# LV_power.net
KiCad netlist of a schematic drawn in Altium Designer
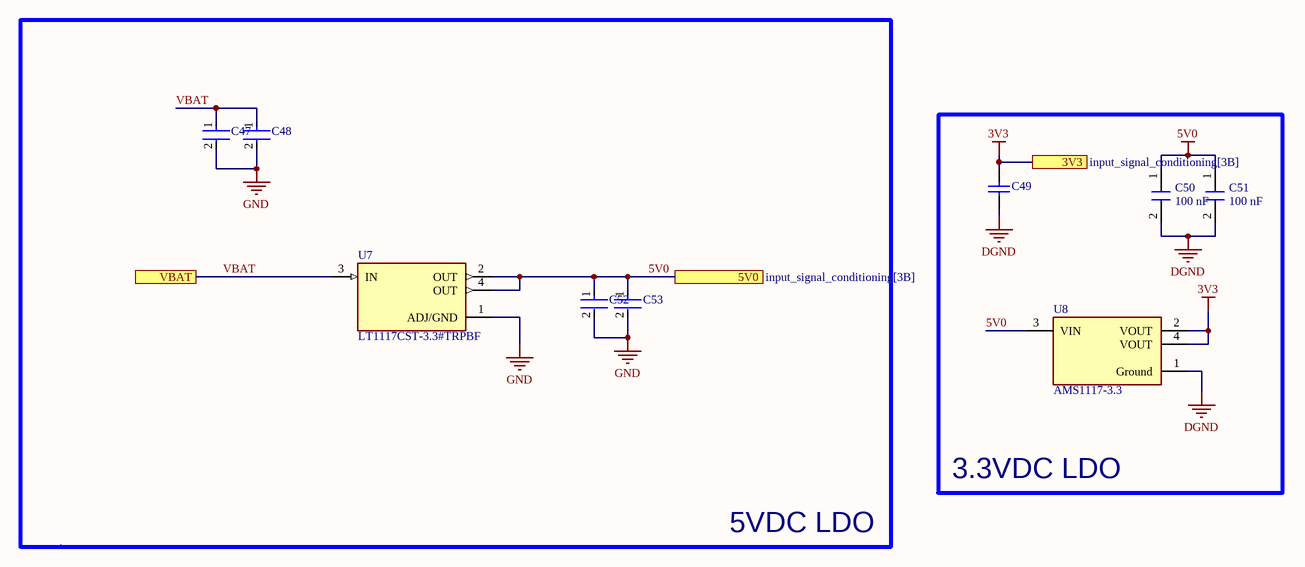
[diagram p0: LV_power.SchDoc]

(export (version "E")
  (design (tool "Eeschema 10.0.6"))
  (components
    (comp (ref "C47")
      (value "CC0805MKX5R8BB226")
      (footprint "FP-CC0805-0_2-1_45-IPC_C")
      (description "CAP CER 22UF 25V X5R 0805")
      (fields (field (name "TOLERANCE") "20%"))
      (libsource (lib "Altium Content Vault") (part "11868f565c42a9108669ba33697ecf6"))
    )
    (comp (ref "C48")
      (value "CC0805MKX5R8BB226")
      (footprint "FP-CC0805-0_2-1_45-IPC_C")
      (description "CAP CER 22UF 25V X5R 0805")
      (fields (field (name "TOLERANCE") "20%"))
      (libsource (lib "Altium Content Vault") (part "11868f565c42a9108669ba33697ecf6"))
    )
    (comp (ref "C49")
      (value "0805ZG106ZAT2A")
      (footprint "CAPC2013X152X50NL20T25")
      (fields (field (name "MANUFACTURER") "AVX Interconnect / Elco"))
      (libsource (lib "Altium Content Vault") (part "CAP"))
    )
    (comp (ref "C50")
      (value "100 nF")
      (footprint "0603_FP")
      (fields (field (name "Comment") "Capacitor_0603"))
      (libsource (lib "RC_sch") (part "Capacitor_0603"))
    )
    (comp (ref "C51")
      (value "100 nF")
      (footprint "0603_FP")
      (fields (field (name "Comment") "Capacitor_0603"))
      (libsource (lib "RC_sch") (part "Capacitor_0603"))
    )
    (comp (ref "C52")
      (value "GRM21BR61A476ME15K")
      (footprint "FP-GRM21B-0_2-e0_2_0_7-IPC_B")
      (description "Chip Multilayer Ceramic Capacitors for General Purpose, 0805, 47uF, X5R, 15%, 20%, 10V")
      (fields (field (name "TOLERANCE") "20%"))
      (libsource (lib "Altium Content Vault") (part "b4654b650e69147ec39a6b967a45e02"))
    )
    (comp (ref "C53")
      (value "GRM21BR61A476ME15K")
      (footprint "FP-GRM21B-0_2-e0_2_0_7-IPC_B")
      (description "Chip Multilayer Ceramic Capacitors for General Purpose, 0805, 47uF, X5R, 15%, 20%, 10V")
      (fields (field (name "TOLERANCE") "20%"))
      (libsource (lib "Altium Content Vault") (part "b4654b650e69147ec39a6b967a45e02"))
    )
    (comp (ref "U7")
      (value "LT1117CST-3.3#TRPBF")
      (footprint "REG_LT1117CST-3.3#TRPBF")
      (description "LT1117 - 800mA Low Dropout Positive Regulators Adjustable and Fixed 2.85V, 3.3V, 5V")
      (fields (field (name "MF") "{'manufacturer': u'Analog Devices Inc.'}"))
      (libsource (lib "LT1117CST-3.3_TRPBF") (part "LT1117CST-3.3#TRPBF"))
    )
    (comp (ref "U8")
      (value "AMS1117-3.3")
      (footprint "FP-AMS1117-IPC_C")
      (description "LDO Voltage Regulators 1A, 3.3V")
      (fields
        (field (name "OCTOPART") "https://octopart.com/ams1117-3.3-advanced+monolithic+systems-25899300")
        (field (name "MANUFACTURER") "Advanced Monolithic Systems")
      )
      (libsource (lib "Altium Content Vault") (part "8bdbb5f8e77002000e30dd2845d0354"))
    )
  )
  (nets
    (net (code "1") (name "/VBAT") (class "Default")
      (node (ref "C47") (pin "1") (pinfunction "1_1") (pintype "passive"))
      (node (ref "C48") (pin "1") (pinfunction "1_1") (pintype "passive"))
      (node (ref "U7") (pin "3") (pinfunction "IN_3") (pintype "input"))
    )
    (net (code "2") (name "3V3") (class "Default")
      (node (ref "C49") (pin "2") (pinfunction "2_2") (pintype "passive"))
      (node (ref "U8") (pin "2") (pinfunction "VOUT_2") (pintype "passive"))
      (node (ref "U8") (pin "4") (pinfunction "VOUT_4") (pintype "passive"))
    )
    (net (code "3") (name "5V0") (class "Default")
      (node (ref "C50") (pin "1") (pinfunction "1_1") (pintype "passive"))
      (node (ref "C51") (pin "1") (pinfunction "1_1") (pintype "passive"))
      (node (ref "C52") (pin "1") (pinfunction "1_1") (pintype "passive"))
      (node (ref "C53") (pin "1") (pinfunction "1_1") (pintype "passive"))
      (node (ref "U7") (pin "2") (pinfunction "OUT_2") (pintype "output"))
      (node (ref "U7") (pin "4") (pinfunction "OUT_4") (pintype "output"))
      (node (ref "U8") (pin "3") (pinfunction "VIN_3") (pintype "power_in"))
    )
    (net (code "4") (name "DGND") (class "Default")
      (node (ref "C49") (pin "1") (pinfunction "1_1") (pintype "passive"))
      (node (ref "C50") (pin "2") (pinfunction "2_2") (pintype "passive"))
      (node (ref "C51") (pin "2") (pinfunction "2_2") (pintype "passive"))
      (node (ref "U8") (pin "1") (pinfunction "Ground_1") (pintype "power_in"))
    )
    (net (code "5") (name "GND") (class "Default")
      (node (ref "C47") (pin "2") (pinfunction "2_2") (pintype "passive"))
      (node (ref "C48") (pin "2") (pinfunction "2_2") (pintype "passive"))
      (node (ref "C52") (pin "2") (pinfunction "2_2") (pintype "passive"))
      (node (ref "C53") (pin "2") (pinfunction "2_2") (pintype "passive"))
      (node (ref "U7") (pin "1") (pinfunction "ADJ/GND_1") (pintype "power_in"))
    )
  )
)
